# Power_BZ_LED_HD.net
KiCad netlist of a schematic drawn in Altium Designer
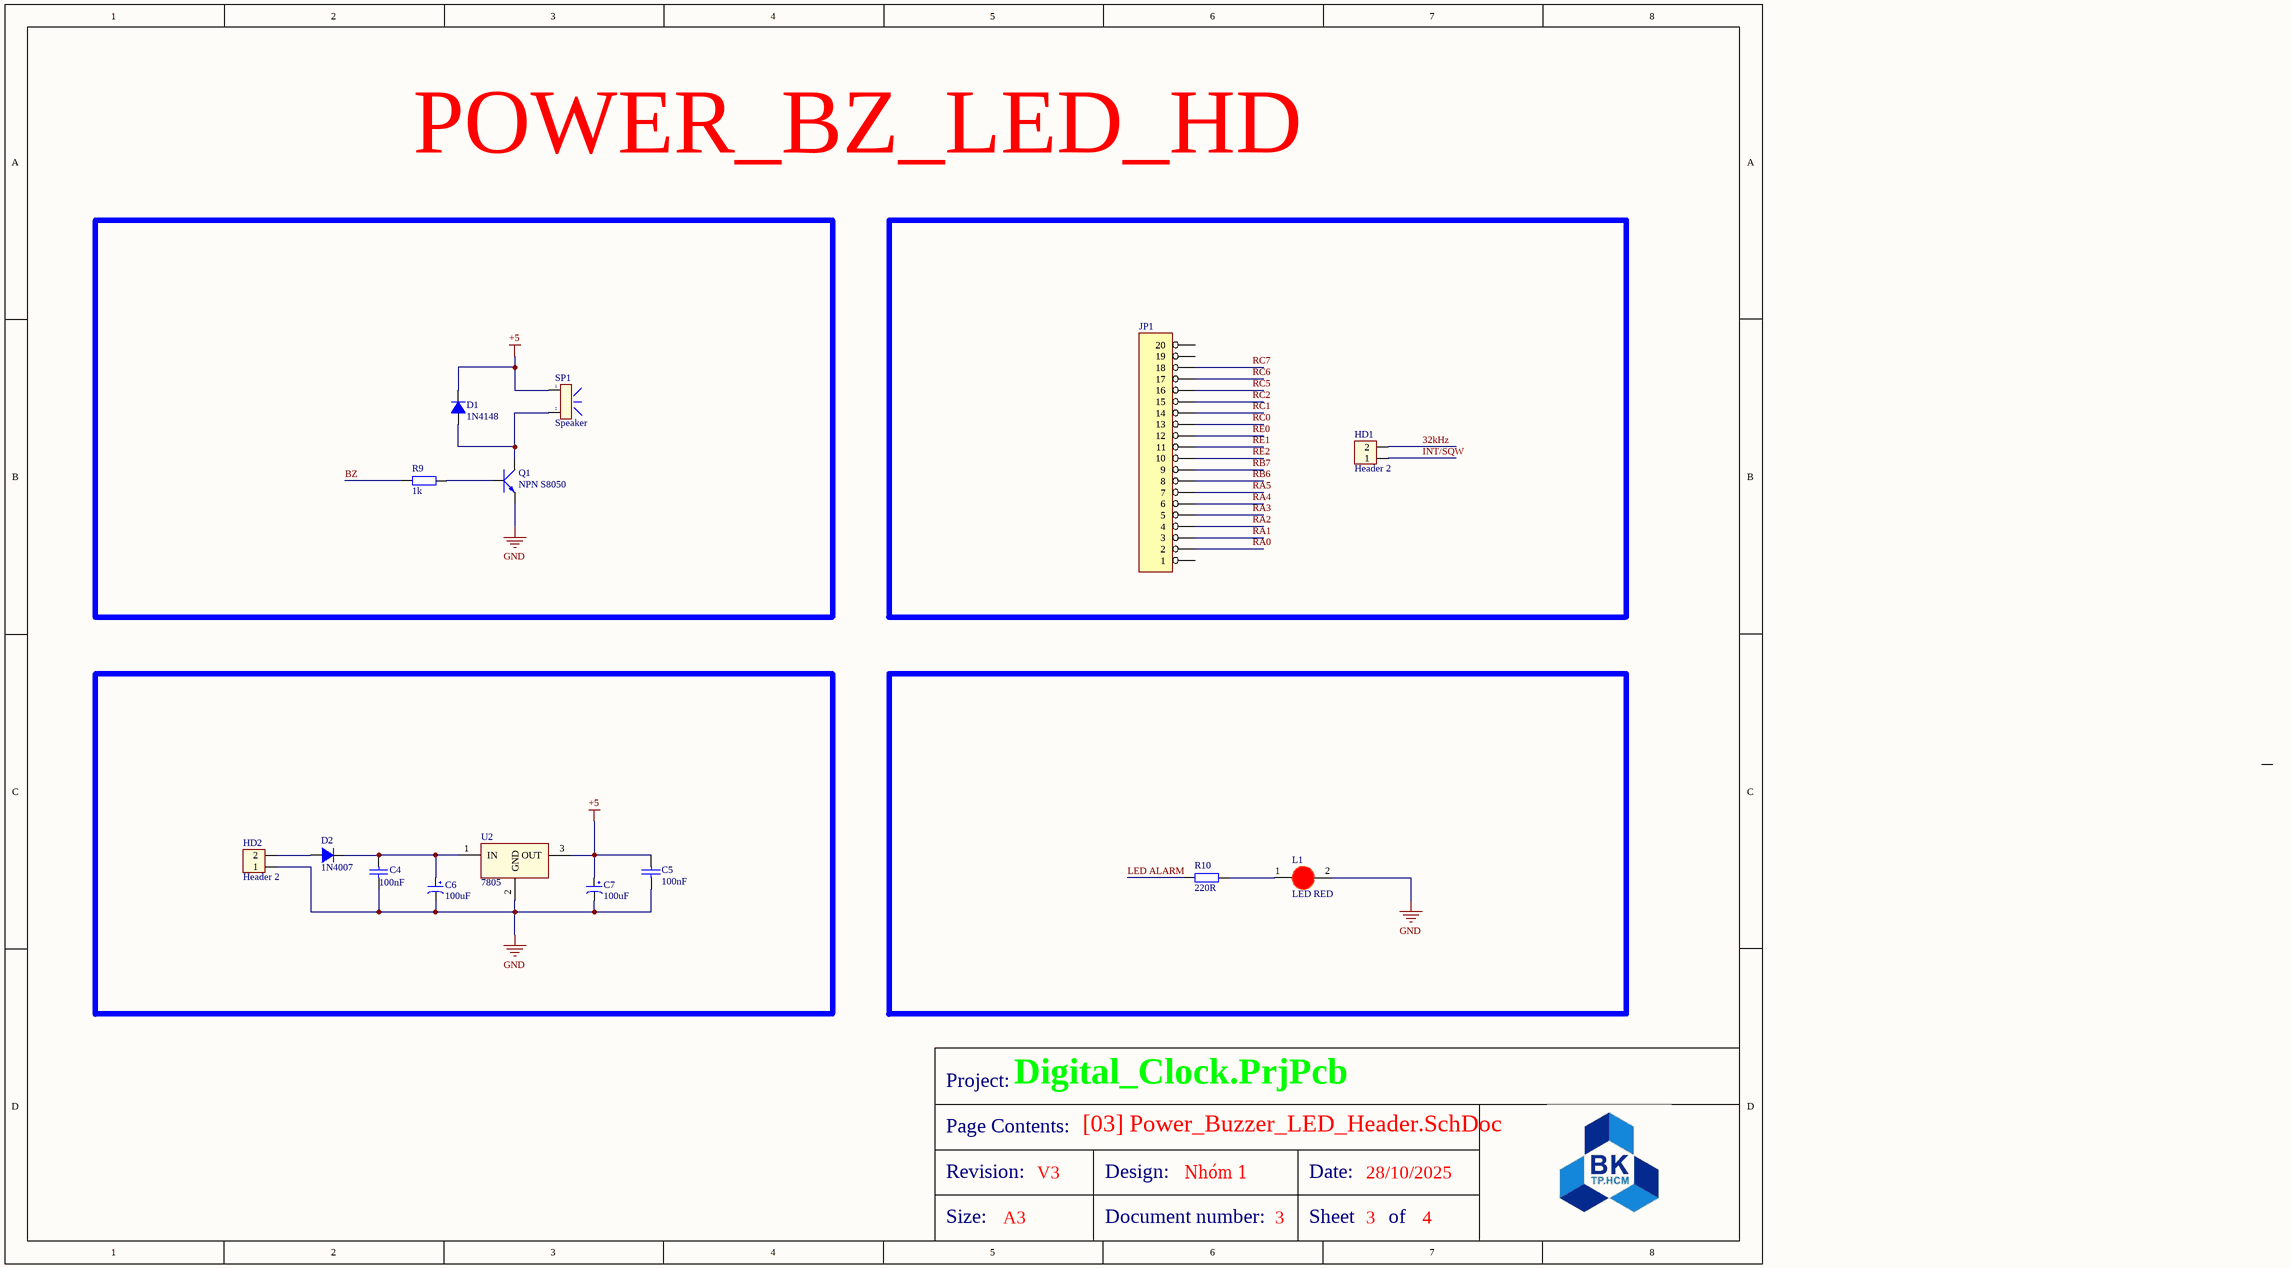
[diagram p0: Power_BZ_LED_HD.SchDoc]

(export (version "E")
  (design (tool "Eeschema 10.0.6"))
  (components
    (comp (ref "C4")
      (value "100nF")
      (footprint "tu gom")
      (description "Cắm")
      (libsource (lib "Capacitor") (part "Tu gom 22pF 50V"))
    )
    (comp (ref "C5")
      (value "100nF")
      (footprint "tu gom")
      (description "Cắm")
      (libsource (lib "Capacitor") (part "Tu gom 22pF 50V"))
    )
    (comp (ref "C6")
      (value "100uF")
      (footprint "tu hoa 6.5mm")
      (description "Cắm")
      (libsource (lib "Capacitor") (part "Tu Hoa 100uF 35V 6x8"))
    )
    (comp (ref "C7")
      (value "100uF")
      (footprint "tu hoa 6.5mm")
      (description "Cắm")
      (libsource (lib "Capacitor") (part "Tu Hoa 100uF 35V 6x8"))
    )
    (comp (ref "D1")
      (value "1N4148")
      (footprint "DIODE 0.5A")
      (description "Cắm")
      (libsource (lib "Diode") (part "Diode 1N4148"))
    )
    (comp (ref "D2")
      (value "1N4007")
      (footprint "DIODE 1A")
      (description "Cắm")
      (libsource (lib "Diode") (part "Diode 1N4007"))
    )
    (comp (ref "HD1")
      (value "Header 2")
      (footprint "HED2")
      (description "Header 2 (Green)")
      (libsource (lib "Cty1") (part "Hed2"))
    )
    (comp (ref "HD2")
      (value "Header 2")
      (footprint "HED2")
      (description "Header 2 (Green)")
      (libsource (lib "Cty1") (part "Hed2"))
    )
    (comp (ref "JP1")
      (value "~")
      (footprint "HDR1X20")
      (description "Header, 20-Pin, Right Angle")
      (libsource (lib "Cty1") (part "Header 20"))
    )
    (comp (ref "L1")
      (value "LED RED")
      (footprint "LED-5MM-RED")
      (description "Cắm")
      (libsource (lib "Led") (part "LED 5mm Do"))
    )
    (comp (ref "Q1")
      (value "NPN S8050")
      (footprint "QTO-92")
      (description "P 600mW, ECB")
      (libsource (lib "syhaunguyen") (part "NPN_ECB"))
    )
    (comp (ref "R9")
      (value "1k")
      (footprint "R1/4W")
      (description "Resistor 1/4W")
      (libsource (lib "My Library") (part "R1/4W"))
    )
    (comp (ref "R10")
      (value "220R")
      (footprint "tro vach 1/4w")
      (description "Cắm")
      (libsource (lib "Resistor") (part "Tro Vach 1/4W 5% 220R"))
    )
    (comp (ref "SP1")
      (value "Speaker")
      (footprint "SPEAKER")
      (description "Speaker Chip")
      (libsource (lib "syhaunguyen") (part "SPK"))
    )
    (comp (ref "U2")
      (value "7805")
      (footprint "QTO-220")
      (description "On ap +, from + 5 to + 24VDC")
      (libsource (lib "syhaunguyen") (part "LM78xx"))
    )
  )
  (nets
    (net (code "1") (name "+5") (class "Default")
      (node (ref "C5") (pin "1") (pinfunction "1_1") (pintype "passive"))
      (node (ref "C7") (pin "1") (pinfunction "1_1") (pintype "passive"))
      (node (ref "D1") (pin "2") (pinfunction "K_2") (pintype "passive"))
      (node (ref "SP1") (pin "1") (pinfunction "1_1") (pintype "passive"))
      (node (ref "U2") (pin "3") (pinfunction "OUT_3") (pintype "passive"))
    )
    (net (code "2") (name "/32kHz") (class "Default")
      (node (ref "HD1") (pin "2") (pinfunction "2_2") (pintype "passive"))
    )
    (net (code "3") (name "/BZ") (class "Default")
      (node (ref "R9") (pin "1") (pinfunction "1_1") (pintype "passive"))
    )
    (net (code "4") (name "/INT{slash}SQW") (class "Default")
      (node (ref "HD1") (pin "1") (pinfunction "1_1") (pintype "passive"))
    )
    (net (code "5") (name "/LED ALARM") (class "Default")
      (node (ref "R10") (pin "1") (pinfunction "1_1") (pintype "passive"))
    )
    (net (code "6") (name "/RA0") (class "Default")
      (node (ref "JP1") (pin "2") (pinfunction "2_2") (pintype "passive"))
    )
    (net (code "7") (name "/RA1") (class "Default")
      (node (ref "JP1") (pin "3") (pinfunction "3_3") (pintype "passive"))
    )
    (net (code "8") (name "/RA2") (class "Default")
      (node (ref "JP1") (pin "4") (pinfunction "4_4") (pintype "passive"))
    )
    (net (code "9") (name "/RA3") (class "Default")
      (node (ref "JP1") (pin "5") (pinfunction "5_5") (pintype "passive"))
    )
    (net (code "10") (name "/RA4") (class "Default")
      (node (ref "JP1") (pin "6") (pinfunction "6_6") (pintype "passive"))
    )
    (net (code "11") (name "/RA5") (class "Default")
      (node (ref "JP1") (pin "7") (pinfunction "7_7") (pintype "passive"))
    )
    (net (code "12") (name "/RB6") (class "Default")
      (node (ref "JP1") (pin "8") (pinfunction "8_8") (pintype "passive"))
    )
    (net (code "13") (name "/RB7") (class "Default")
      (node (ref "JP1") (pin "9") (pinfunction "9_9") (pintype "passive"))
    )
    (net (code "14") (name "/RC0") (class "Default")
      (node (ref "JP1") (pin "13") (pinfunction "13_13") (pintype "passive"))
    )
    (net (code "15") (name "/RC1") (class "Default")
      (node (ref "JP1") (pin "14") (pinfunction "14_14") (pintype "passive"))
    )
    (net (code "16") (name "/RC2") (class "Default")
      (node (ref "JP1") (pin "15") (pinfunction "15_15") (pintype "passive"))
    )
    (net (code "17") (name "/RC5") (class "Default")
      (node (ref "JP1") (pin "16") (pinfunction "16_16") (pintype "passive"))
    )
    (net (code "18") (name "/RC6") (class "Default")
      (node (ref "JP1") (pin "17") (pinfunction "17_17") (pintype "passive"))
    )
    (net (code "19") (name "/RC7") (class "Default")
      (node (ref "JP1") (pin "18") (pinfunction "18_18") (pintype "passive"))
    )
    (net (code "20") (name "/RE0") (class "Default")
      (node (ref "JP1") (pin "12") (pinfunction "12_12") (pintype "passive"))
    )
    (net (code "21") (name "/RE1") (class "Default")
      (node (ref "JP1") (pin "11") (pinfunction "11_11") (pintype "passive"))
    )
    (net (code "22") (name "/RE2") (class "Default")
      (node (ref "JP1") (pin "10") (pinfunction "10_10") (pintype "passive"))
    )
    (net (code "23") (name "GND") (class "Default")
      (node (ref "C4") (pin "2") (pinfunction "2_2") (pintype "passive"))
      (node (ref "C5") (pin "2") (pinfunction "2_2") (pintype "passive"))
      (node (ref "C6") (pin "2") (pinfunction "2_2") (pintype "passive"))
      (node (ref "C7") (pin "2") (pinfunction "2_2") (pintype "passive"))
      (node (ref "HD2") (pin "1") (pinfunction "1_1") (pintype "passive"))
      (node (ref "L1") (pin "2") (pinfunction "K_2") (pintype "passive"))
      (node (ref "Q1") (pin "1") (pinfunction "E_1") (pintype "passive"))
      (node (ref "U2") (pin "2") (pinfunction "GND_2") (pintype "passive"))
    )
    (net (code "24") (name "Net-(D1-A)") (class "Default")
      (node (ref "D1") (pin "1") (pinfunction "A_1") (pintype "passive"))
      (node (ref "Q1") (pin "2") (pinfunction "C_2") (pintype "passive"))
      (node (ref "SP1") (pin "2") (pinfunction "2_2") (pintype "passive"))
    )
    (net (code "25") (name "Net-(D2-A)") (class "Default")
      (node (ref "D2") (pin "1") (pinfunction "A_1") (pintype "passive"))
      (node (ref "HD2") (pin "2") (pinfunction "2_2") (pintype "passive"))
    )
    (net (code "26") (name "Net-(D2-K)") (class "Default")
      (node (ref "C4") (pin "1") (pinfunction "1_1") (pintype "passive"))
      (node (ref "C6") (pin "1") (pinfunction "1_1") (pintype "passive"))
      (node (ref "D2") (pin "2") (pinfunction "K_2") (pintype "passive"))
      (node (ref "U2") (pin "1") (pinfunction "IN_1") (pintype "passive"))
    )
    (net (code "27") (name "Net-(L1-A)") (class "Default")
      (node (ref "L1") (pin "1") (pinfunction "A_1") (pintype "passive"))
      (node (ref "R10") (pin "2") (pinfunction "2_2") (pintype "passive"))
    )
    (net (code "28") (name "Net-(Q1-B)") (class "Default")
      (node (ref "Q1") (pin "3") (pinfunction "B_3") (pintype "passive"))
      (node (ref "R9") (pin "2") (pinfunction "2_2") (pintype "passive"))
    )
    (net (code "29") (name "unconnected-(JP1-Pad1)") (class "Default")
      (node (ref "JP1") (pin "1") (pinfunction "1_1") (pintype "passive"))
    )
    (net (code "30") (name "unconnected-(JP1-Pad19)") (class "Default")
      (node (ref "JP1") (pin "19") (pinfunction "19_19") (pintype "passive"))
    )
    (net (code "31") (name "unconnected-(JP1-Pad20)") (class "Default")
      (node (ref "JP1") (pin "20") (pinfunction "20_20") (pintype "passive"))
    )
  )
)
